# nodemcurelay.net
KiCad netlist of a schematic drawn in EAGLE
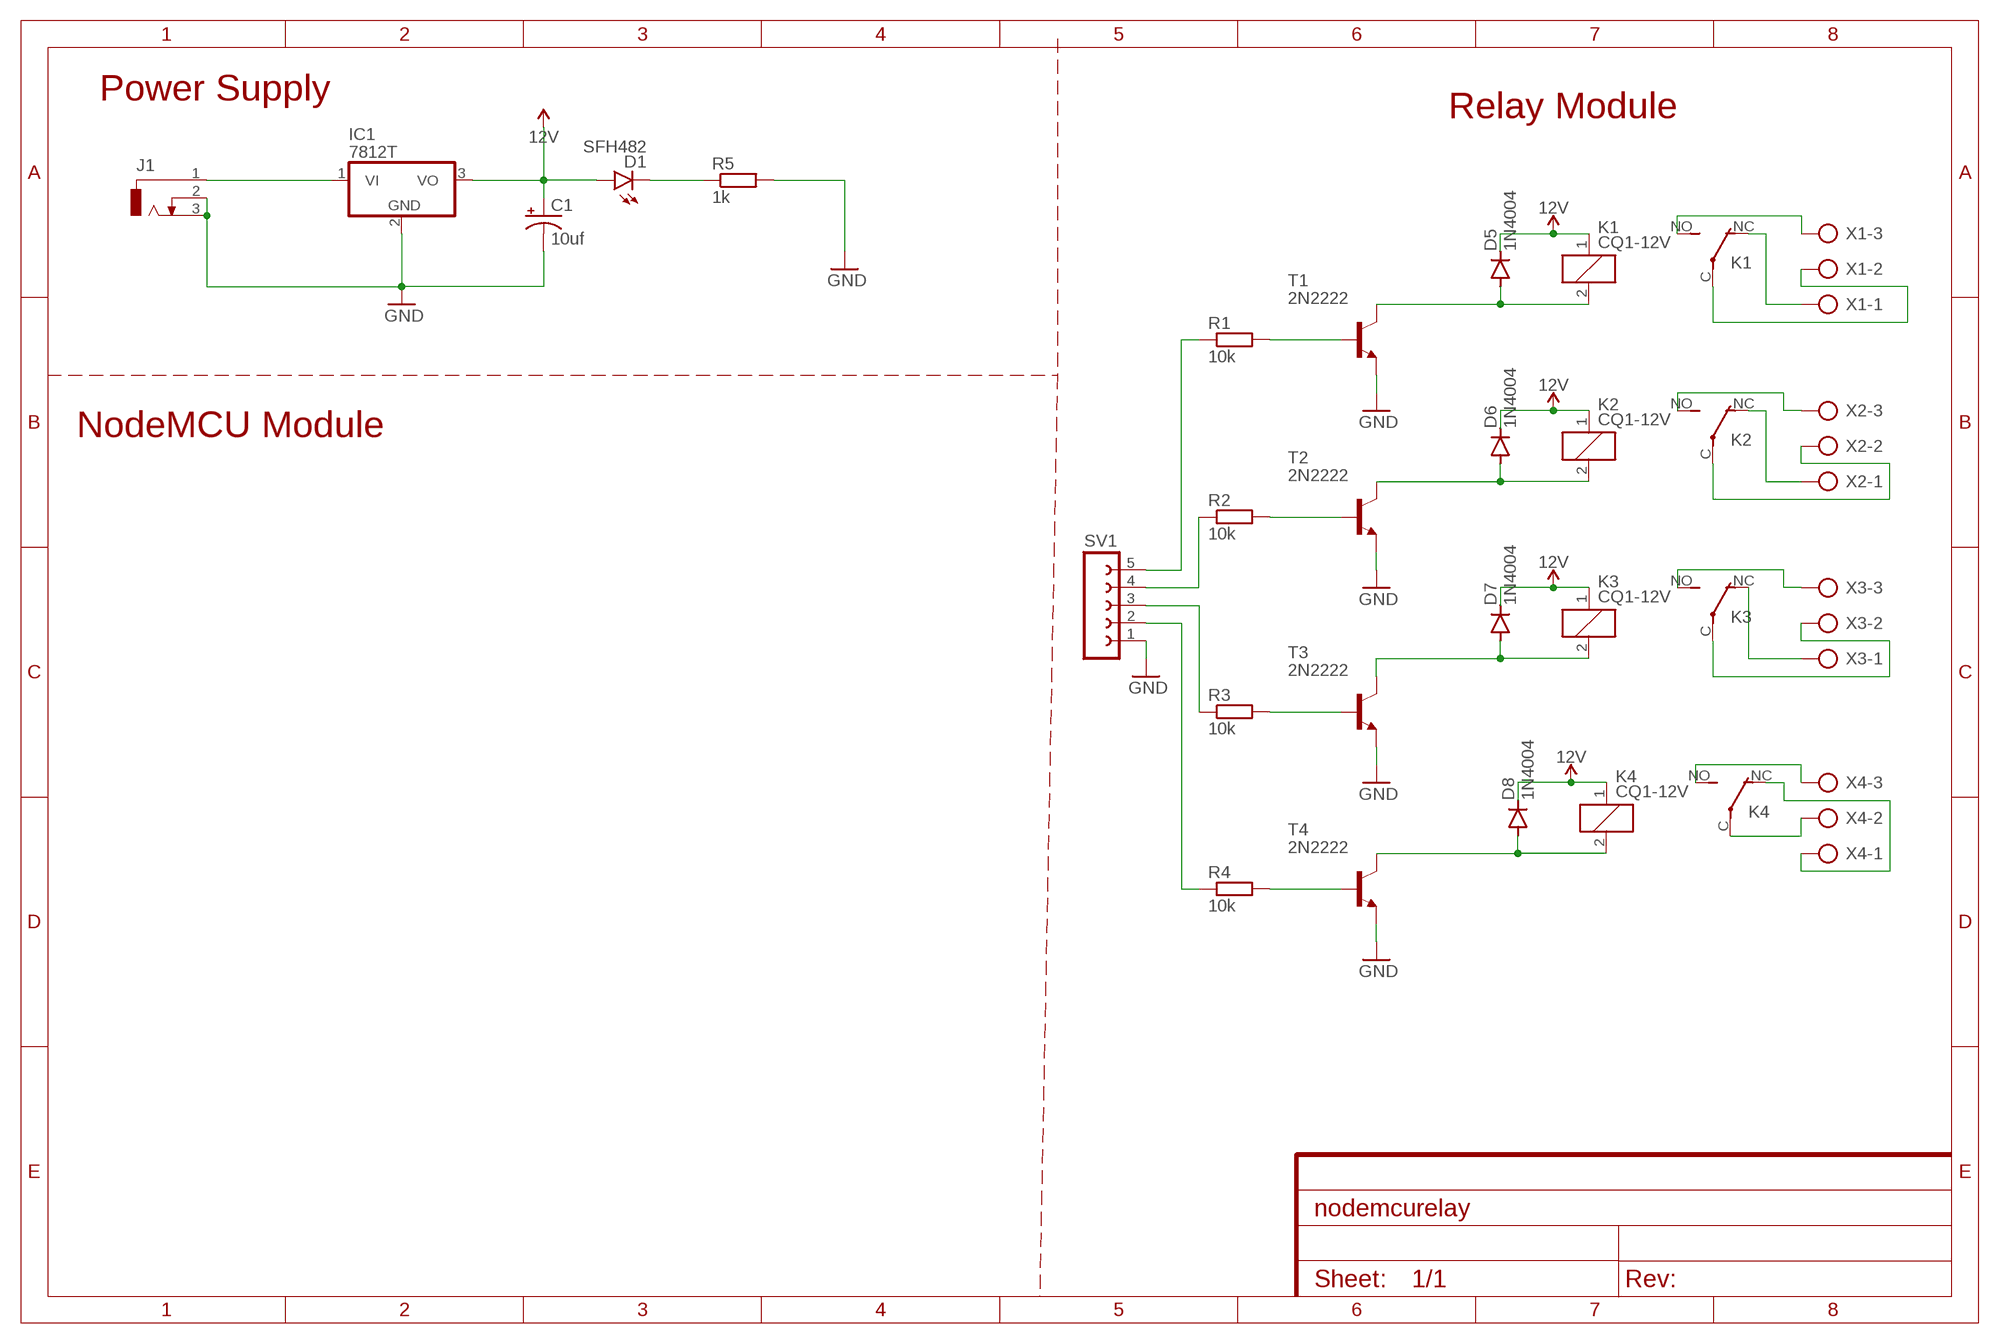
[diagram p0: schematic, sheet 1]

(export (version "E")
  (design (tool "Eeschema 10.0.6"))
  (components
    (comp (ref "C1")
      (value "10uf")
      (footprint "eagle-import:E3,5-8")
      (libsource (lib "eagle-import") (part "CPOL-USE3.5-8"))
    )
    (comp (ref "D1")
      (value "SFH482")
      (footprint "eagle-import:SFH482")
      (libsource (lib "eagle-import") (part "SFH482"))
    )
    (comp (ref "D5")
      (value "1N4004")
      (footprint "eagle-import:DO41-10")
      (libsource (lib "eagle-import") (part "1N4004"))
    )
    (comp (ref "D6")
      (value "1N4004")
      (footprint "eagle-import:DO41-10")
      (libsource (lib "eagle-import") (part "1N4004"))
    )
    (comp (ref "D7")
      (value "1N4004")
      (footprint "eagle-import:DO41-10")
      (libsource (lib "eagle-import") (part "1N4004"))
    )
    (comp (ref "D8")
      (value "1N4004")
      (footprint "eagle-import:DO41-10")
      (libsource (lib "eagle-import") (part "1N4004"))
    )
    (comp (ref "IC1")
      (value "7812T")
      (footprint "eagle-import:TO220H")
      (libsource (lib "eagle-import") (part "78T12"))
    )
    (comp (ref "J1")
      (value "DCJ0303")
      (footprint "eagle-import:DCJ0303")
      (libsource (lib "eagle-import") (part "DCJ0303"))
    )
    (comp (ref "K1")
      (value "CQ1-12V")
      (footprint "eagle-import:CQ1")
      (libsource (lib "eagle-import") (part "CQ1-12V"))
    )
    (comp (ref "K2")
      (value "CQ1-12V")
      (footprint "eagle-import:CQ1")
      (libsource (lib "eagle-import") (part "CQ1-12V"))
    )
    (comp (ref "K3")
      (value "CQ1-12V")
      (footprint "eagle-import:CQ1")
      (libsource (lib "eagle-import") (part "CQ1-12V"))
    )
    (comp (ref "K4")
      (value "CQ1-12V")
      (footprint "eagle-import:CQ1")
      (libsource (lib "eagle-import") (part "CQ1-12V"))
    )
    (comp (ref "R1")
      (value "10k")
      (footprint "eagle-import:0207_7")
      (libsource (lib "eagle-import") (part "R-EU_0207/7"))
    )
    (comp (ref "R2")
      (value "10k")
      (footprint "eagle-import:0207_7")
      (libsource (lib "eagle-import") (part "R-EU_0207/7"))
    )
    (comp (ref "R3")
      (value "10k")
      (footprint "eagle-import:0207_7")
      (libsource (lib "eagle-import") (part "R-EU_0207/7"))
    )
    (comp (ref "R4")
      (value "10k")
      (footprint "eagle-import:0207_7")
      (libsource (lib "eagle-import") (part "R-EU_0207/7"))
    )
    (comp (ref "R5")
      (value "1k")
      (footprint "eagle-import:0207_7")
      (libsource (lib "eagle-import") (part "R-EU_0207/7"))
    )
    (comp (ref "SV1")
      (value "FE05-1")
      (footprint "eagle-import:FE05-1")
      (libsource (lib "eagle-import") (part "FE05-1"))
    )
    (comp (ref "T1")
      (value "2N2222")
      (footprint "eagle-import:TO92-EBC-OVAL")
      (libsource (lib "eagle-import") (part "2N2222"))
    )
    (comp (ref "T2")
      (value "2N2222")
      (footprint "eagle-import:TO92-EBC-OVAL")
      (libsource (lib "eagle-import") (part "2N2222"))
    )
    (comp (ref "T3")
      (value "2N2222")
      (footprint "eagle-import:TO92-EBC-OVAL")
      (libsource (lib "eagle-import") (part "2N2222"))
    )
    (comp (ref "T4")
      (value "2N2222")
      (footprint "eagle-import:TO92-EBC-OVAL")
      (libsource (lib "eagle-import") (part "2N2222"))
    )
    (comp (ref "X1")
      (value "AK300/3")
      (footprint "eagle-import:AK300_3")
      (libsource (lib "eagle-import") (part "AK300/3"))
    )
    (comp (ref "X2")
      (value "AK300/3")
      (footprint "eagle-import:AK300_3")
      (libsource (lib "eagle-import") (part "AK300/3"))
    )
    (comp (ref "X3")
      (value "AK300/3")
      (footprint "eagle-import:AK300_3")
      (libsource (lib "eagle-import") (part "AK300/3"))
    )
    (comp (ref "X4")
      (value "AK300/3")
      (footprint "eagle-import:AK300_3")
      (libsource (lib "eagle-import") (part "AK300/3"))
    )
  )
  (nets
    (net (code "1") (name "12V") (class "Default")
      (node (ref "C1") (pin "+") (pinfunction "+_+") (pintype "passive"))
      (node (ref "D1") (pin "A") (pinfunction "A_A") (pintype "passive"))
      (node (ref "D5") (pin "C") (pinfunction "C_C") (pintype "passive"))
      (node (ref "D6") (pin "C") (pinfunction "C_C") (pintype "passive"))
      (node (ref "D7") (pin "C") (pinfunction "C_C") (pintype "passive"))
      (node (ref "D8") (pin "C") (pinfunction "C_C") (pintype "passive"))
      (node (ref "IC1") (pin "3") (pinfunction "VO_3") (pintype "passive"))
      (node (ref "K1") (pin "1") (pinfunction "1_1") (pintype "passive"))
      (node (ref "K2") (pin "1") (pinfunction "1_1") (pintype "passive"))
      (node (ref "K3") (pin "1") (pinfunction "1_1") (pintype "passive"))
      (node (ref "K4") (pin "1") (pinfunction "1_1") (pintype "passive"))
    )
    (net (code "2") (name "GND") (class "Default")
      (node (ref "C1") (pin "-") (pinfunction "-_-") (pintype "passive"))
      (node (ref "IC1") (pin "2") (pinfunction "GND_2") (pintype "passive"))
      (node (ref "J1") (pin "2") (pinfunction "2_2") (pintype "passive"))
      (node (ref "J1") (pin "3") (pinfunction "3_3") (pintype "passive"))
      (node (ref "R5") (pin "2") (pinfunction "2_2") (pintype "passive"))
      (node (ref "SV1") (pin "1") (pinfunction "1_1") (pintype "passive"))
      (node (ref "T1") (pin "E") (pinfunction "E_E") (pintype "passive"))
      (node (ref "T2") (pin "E") (pinfunction "E_E") (pintype "passive"))
      (node (ref "T3") (pin "E") (pinfunction "E_E") (pintype "passive"))
      (node (ref "T4") (pin "E") (pinfunction "E_E") (pintype "passive"))
    )
    (net (code "3") (name "Net-(D1-C)") (class "Default")
      (node (ref "D1") (pin "K") (pinfunction "C_K") (pintype "passive"))
      (node (ref "R5") (pin "1") (pinfunction "1_1") (pintype "passive"))
    )
    (net (code "4") (name "Net-(D5-PadA)") (class "Default")
      (node (ref "D5") (pin "A") (pinfunction "A_A") (pintype "passive"))
      (node (ref "K1") (pin "2") (pinfunction "2_2") (pintype "passive"))
      (node (ref "T1") (pin "C") (pinfunction "C_C") (pintype "passive"))
    )
    (net (code "5") (name "Net-(D6-PadA)") (class "Default")
      (node (ref "D6") (pin "A") (pinfunction "A_A") (pintype "passive"))
      (node (ref "K2") (pin "2") (pinfunction "2_2") (pintype "passive"))
      (node (ref "T2") (pin "C") (pinfunction "C_C") (pintype "passive"))
    )
    (net (code "6") (name "Net-(D7-PadA)") (class "Default")
      (node (ref "D7") (pin "A") (pinfunction "A_A") (pintype "passive"))
      (node (ref "K3") (pin "2") (pinfunction "2_2") (pintype "passive"))
      (node (ref "T3") (pin "C") (pinfunction "C_C") (pintype "passive"))
    )
    (net (code "7") (name "Net-(D8-PadA)") (class "Default")
      (node (ref "D8") (pin "A") (pinfunction "A_A") (pintype "passive"))
      (node (ref "K4") (pin "2") (pinfunction "2_2") (pintype "passive"))
      (node (ref "T4") (pin "C") (pinfunction "C_C") (pintype "passive"))
    )
    (net (code "8") (name "Net-(IC1-VI)") (class "Default")
      (node (ref "IC1") (pin "1") (pinfunction "VI_1") (pintype "input"))
      (node (ref "J1") (pin "1") (pinfunction "1_1") (pintype "passive"))
    )
    (net (code "9") (name "Net-(K1B-O)") (class "Default")
      (node (ref "K1") (pin "NC") (pinfunction "O_NC") (pintype "passive"))
      (node (ref "X1") (pin "1") (pinfunction "KL_1") (pintype "passive"))
    )
    (net (code "10") (name "Net-(K1B-P)") (class "Default")
      (node (ref "K1") (pin "C") (pinfunction "P_C") (pintype "passive"))
      (node (ref "X1") (pin "2") (pinfunction "KL_2") (pintype "passive"))
    )
    (net (code "11") (name "Net-(K1B-S)") (class "Default")
      (node (ref "K1") (pin "NO") (pinfunction "S_NO") (pintype "passive"))
      (node (ref "X1") (pin "3") (pinfunction "KL_3") (pintype "passive"))
    )
    (net (code "12") (name "Net-(K2B-O)") (class "Default")
      (node (ref "K2") (pin "NC") (pinfunction "O_NC") (pintype "passive"))
      (node (ref "X2") (pin "1") (pinfunction "KL_1") (pintype "passive"))
    )
    (net (code "13") (name "Net-(K2B-P)") (class "Default")
      (node (ref "K2") (pin "C") (pinfunction "P_C") (pintype "passive"))
      (node (ref "X2") (pin "2") (pinfunction "KL_2") (pintype "passive"))
    )
    (net (code "14") (name "Net-(K2B-S)") (class "Default")
      (node (ref "K2") (pin "NO") (pinfunction "S_NO") (pintype "passive"))
      (node (ref "X2") (pin "3") (pinfunction "KL_3") (pintype "passive"))
    )
    (net (code "15") (name "Net-(K3B-O)") (class "Default")
      (node (ref "K3") (pin "NC") (pinfunction "O_NC") (pintype "passive"))
      (node (ref "X3") (pin "1") (pinfunction "KL_1") (pintype "passive"))
    )
    (net (code "16") (name "Net-(K3B-P)") (class "Default")
      (node (ref "K3") (pin "C") (pinfunction "P_C") (pintype "passive"))
      (node (ref "X3") (pin "2") (pinfunction "KL_2") (pintype "passive"))
    )
    (net (code "17") (name "Net-(K3B-S)") (class "Default")
      (node (ref "K3") (pin "NO") (pinfunction "S_NO") (pintype "passive"))
      (node (ref "X3") (pin "3") (pinfunction "KL_3") (pintype "passive"))
    )
    (net (code "18") (name "Net-(K4B-O)") (class "Default")
      (node (ref "K4") (pin "NC") (pinfunction "O_NC") (pintype "passive"))
      (node (ref "X4") (pin "1") (pinfunction "KL_1") (pintype "passive"))
    )
    (net (code "19") (name "Net-(K4B-P)") (class "Default")
      (node (ref "K4") (pin "C") (pinfunction "P_C") (pintype "passive"))
      (node (ref "X4") (pin "2") (pinfunction "KL_2") (pintype "passive"))
    )
    (net (code "20") (name "Net-(K4B-S)") (class "Default")
      (node (ref "K4") (pin "NO") (pinfunction "S_NO") (pintype "passive"))
      (node (ref "X4") (pin "3") (pinfunction "KL_3") (pintype "passive"))
    )
    (net (code "21") (name "Net-(R1-Pad1)") (class "Default")
      (node (ref "R1") (pin "1") (pinfunction "1_1") (pintype "passive"))
      (node (ref "SV1") (pin "5") (pinfunction "5_5") (pintype "passive"))
    )
    (net (code "22") (name "Net-(R1-Pad2)") (class "Default")
      (node (ref "R1") (pin "2") (pinfunction "2_2") (pintype "passive"))
      (node (ref "T1") (pin "B") (pinfunction "B_B") (pintype "passive"))
    )
    (net (code "23") (name "Net-(R2-Pad1)") (class "Default")
      (node (ref "R2") (pin "1") (pinfunction "1_1") (pintype "passive"))
      (node (ref "SV1") (pin "4") (pinfunction "4_4") (pintype "passive"))
    )
    (net (code "24") (name "Net-(R2-Pad2)") (class "Default")
      (node (ref "R2") (pin "2") (pinfunction "2_2") (pintype "passive"))
      (node (ref "T2") (pin "B") (pinfunction "B_B") (pintype "passive"))
    )
    (net (code "25") (name "Net-(R3-Pad1)") (class "Default")
      (node (ref "R3") (pin "1") (pinfunction "1_1") (pintype "passive"))
      (node (ref "SV1") (pin "3") (pinfunction "3_3") (pintype "passive"))
    )
    (net (code "26") (name "Net-(R3-Pad2)") (class "Default")
      (node (ref "R3") (pin "2") (pinfunction "2_2") (pintype "passive"))
      (node (ref "T3") (pin "B") (pinfunction "B_B") (pintype "passive"))
    )
    (net (code "27") (name "Net-(R4-Pad1)") (class "Default")
      (node (ref "R4") (pin "1") (pinfunction "1_1") (pintype "passive"))
      (node (ref "SV1") (pin "2") (pinfunction "2_2") (pintype "passive"))
    )
    (net (code "28") (name "Net-(R4-Pad2)") (class "Default")
      (node (ref "R4") (pin "2") (pinfunction "2_2") (pintype "passive"))
      (node (ref "T4") (pin "B") (pinfunction "B_B") (pintype "passive"))
    )
  )
)
